# arduino_wireless_shield_rev_1_0.net
KiCad netlist of a schematic drawn in EAGLE
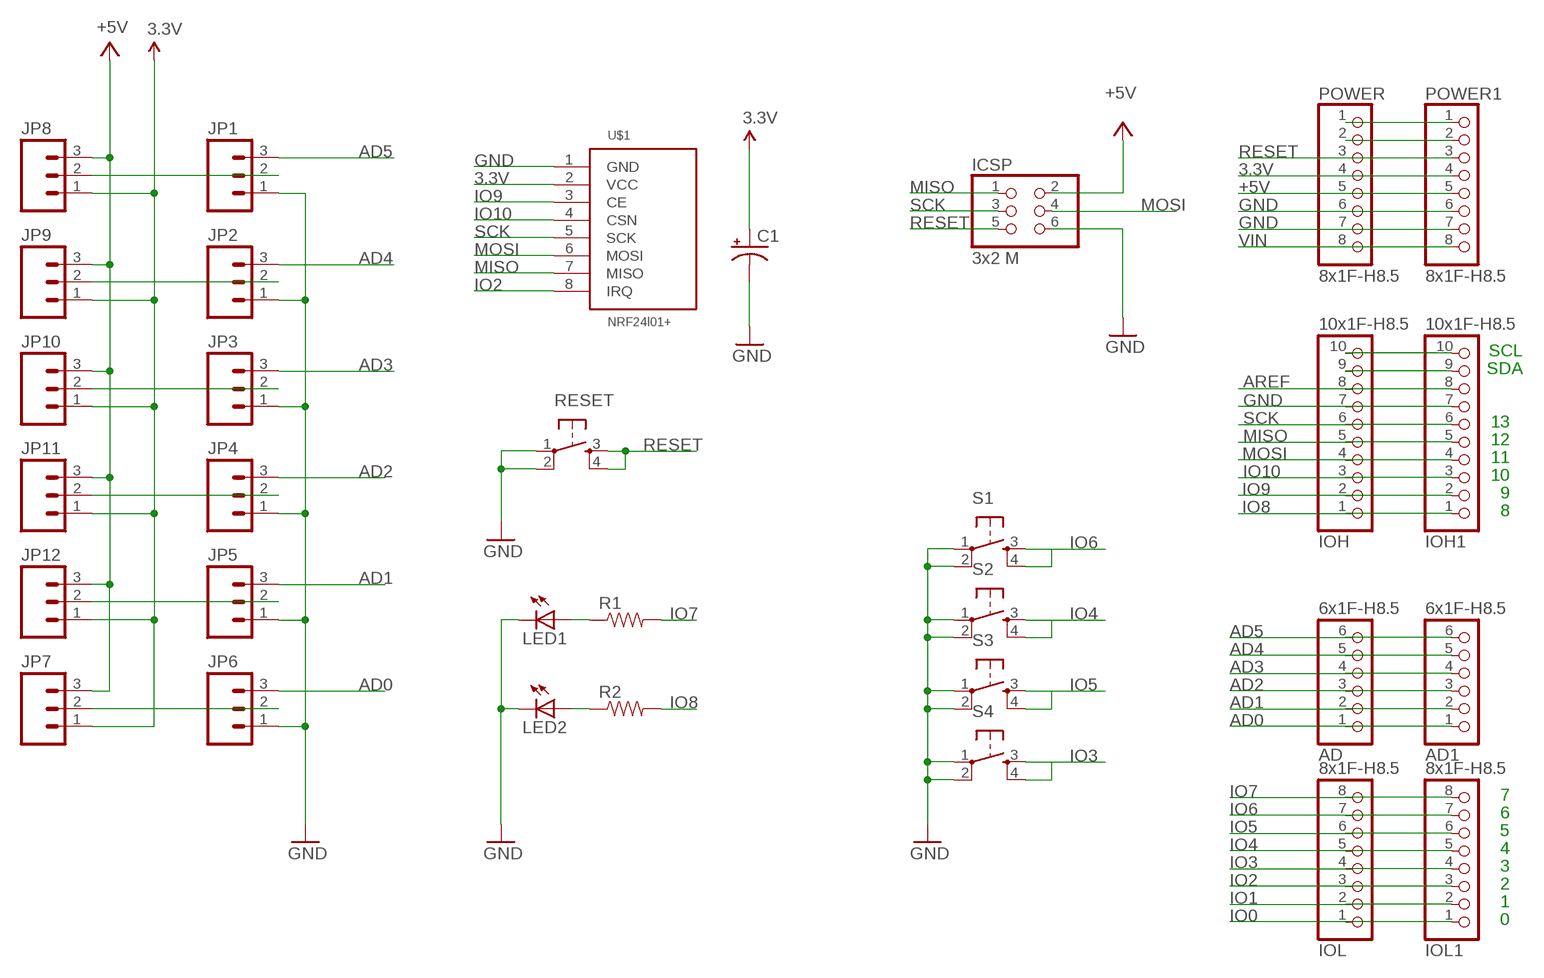
[diagram p0: schematic, sheet 1]

(export (version "E")
  (design (tool "Eeschema 10.0.6"))
  (components
    (comp (ref "AD")
      (value "6x1F-H8.5")
      (footprint "eagle-import:1X06")
      (libsource (lib "eagle-import") (part "PINHD-1X6"))
    )
    (comp (ref "AD1")
      (value "6x1F-H8.5")
      (footprint "eagle-import:1X06")
      (libsource (lib "eagle-import") (part "PINHD-1X6"))
    )
    (comp (ref "C1")
      (value "CPOL-USTT2D7")
      (footprint "eagle-import:TT2D7")
      (libsource (lib "eagle-import") (part "CPOL-USTT2D7"))
    )
    (comp (ref "ICSP")
      (value "3x2 M")
      (footprint "eagle-import:2X03")
      (libsource (lib "eagle-import") (part "PINHD-2X3"))
    )
    (comp (ref "IOH")
      (value "10x1F-H8.5")
      (footprint "eagle-import:1X10")
      (libsource (lib "eagle-import") (part "PINHD-1X10_ARD"))
    )
    (comp (ref "IOH1")
      (value "10x1F-H8.5")
      (footprint "eagle-import:1X10")
      (libsource (lib "eagle-import") (part "PINHD-1X10_ARD"))
    )
    (comp (ref "IOL")
      (value "8x1F-H8.5")
      (footprint "eagle-import:1X08")
      (libsource (lib "eagle-import") (part "PINHD-1X8"))
    )
    (comp (ref "IOL1")
      (value "8x1F-H8.5")
      (footprint "eagle-import:1X08")
      (libsource (lib "eagle-import") (part "PINHD-1X8"))
    )
    (comp (ref "JP1")
      (value "M03PTH")
      (footprint "eagle-import:1X03")
      (libsource (lib "eagle-import") (part "M03PTH"))
    )
    (comp (ref "JP2")
      (value "M03PTH")
      (footprint "eagle-import:1X03")
      (libsource (lib "eagle-import") (part "M03PTH"))
    )
    (comp (ref "JP3")
      (value "M03PTH")
      (footprint "eagle-import:1X03")
      (libsource (lib "eagle-import") (part "M03PTH"))
    )
    (comp (ref "JP4")
      (value "M03PTH")
      (footprint "eagle-import:1X03")
      (libsource (lib "eagle-import") (part "M03PTH"))
    )
    (comp (ref "JP5")
      (value "M03PTH")
      (footprint "eagle-import:1X03")
      (libsource (lib "eagle-import") (part "M03PTH"))
    )
    (comp (ref "JP6")
      (value "M03PTH")
      (footprint "eagle-import:1X03")
      (libsource (lib "eagle-import") (part "M03PTH"))
    )
    (comp (ref "JP7")
      (value "M03PTH")
      (footprint "eagle-import:1X03")
      (libsource (lib "eagle-import") (part "M03PTH"))
    )
    (comp (ref "JP8")
      (value "M03PTH")
      (footprint "eagle-import:1X03")
      (libsource (lib "eagle-import") (part "M03PTH"))
    )
    (comp (ref "JP9")
      (value "M03PTH")
      (footprint "eagle-import:1X03")
      (libsource (lib "eagle-import") (part "M03PTH"))
    )
    (comp (ref "JP10")
      (value "M03PTH")
      (footprint "eagle-import:1X03")
      (libsource (lib "eagle-import") (part "M03PTH"))
    )
    (comp (ref "JP11")
      (value "M03PTH")
      (footprint "eagle-import:1X03")
      (libsource (lib "eagle-import") (part "M03PTH"))
    )
    (comp (ref "JP12")
      (value "M03PTH")
      (footprint "eagle-import:1X03")
      (libsource (lib "eagle-import") (part "M03PTH"))
    )
    (comp (ref "LED1")
      (value "LED5MM")
      (footprint "eagle-import:LED5MM")
      (libsource (lib "eagle-import") (part "LED5MM"))
    )
    (comp (ref "LED2")
      (value "LED5MM")
      (footprint "eagle-import:LED5MM")
      (libsource (lib "eagle-import") (part "LED5MM"))
    )
    (comp (ref "POWER")
      (value "8x1F-H8.5")
      (footprint "eagle-import:1X08")
      (libsource (lib "eagle-import") (part "PINHD-1X8"))
    )
    (comp (ref "POWER1")
      (value "8x1F-H8.5")
      (footprint "eagle-import:1X08")
      (libsource (lib "eagle-import") (part "PINHD-1X8"))
    )
    (comp (ref "R1")
      (value "RESISTORPTH-1/4W")
      (footprint "eagle-import:AXIAL-0.4")
      (libsource (lib "eagle-import") (part "RESISTORPTH-1/4W"))
    )
    (comp (ref "R2")
      (value "RESISTORPTH-1/4W")
      (footprint "eagle-import:AXIAL-0.4")
      (libsource (lib "eagle-import") (part "RESISTORPTH-1/4W"))
    )
    (comp (ref "RESET")
      (value "TAC_SWITCHPTH")
      (footprint "eagle-import:TACTILE-PTH")
      (libsource (lib "eagle-import") (part "TAC_SWITCHPTH"))
    )
    (comp (ref "S1")
      (value "TAC_SWITCHPTH")
      (footprint "eagle-import:TACTILE-PTH")
      (libsource (lib "eagle-import") (part "TAC_SWITCHPTH"))
    )
    (comp (ref "S2")
      (value "TAC_SWITCHPTH")
      (footprint "eagle-import:TACTILE-PTH")
      (libsource (lib "eagle-import") (part "TAC_SWITCHPTH"))
    )
    (comp (ref "S3")
      (value "TAC_SWITCHPTH")
      (footprint "eagle-import:TACTILE-PTH")
      (libsource (lib "eagle-import") (part "TAC_SWITCHPTH"))
    )
    (comp (ref "S4")
      (value "TAC_SWITCHPTH")
      (footprint "eagle-import:TACTILE-PTH")
      (libsource (lib "eagle-import") (part "TAC_SWITCHPTH"))
    )
    (comp (ref "U$1")
      (value "NRF24L01+_MODULE")
      (footprint "eagle-import:NRF24L01+MODULE")
      (libsource (lib "eagle-import") (part "NRF24L01+_MODULE"))
    )
  )
  (nets
    (net (code "1") (name "+5V") (class "Default")
      (node (ref "ICSP") (pin "2") (pinfunction "2_2") (pintype "passive"))
      (node (ref "JP10") (pin "3") (pinfunction "3_3") (pintype "passive"))
      (node (ref "JP11") (pin "3") (pinfunction "3_3") (pintype "passive"))
      (node (ref "JP12") (pin "3") (pinfunction "3_3") (pintype "passive"))
      (node (ref "JP7") (pin "3") (pinfunction "3_3") (pintype "passive"))
      (node (ref "JP8") (pin "3") (pinfunction "3_3") (pintype "passive"))
      (node (ref "JP9") (pin "3") (pinfunction "3_3") (pintype "passive"))
      (node (ref "POWER") (pin "5") (pinfunction "5_5") (pintype "passive"))
      (node (ref "POWER1") (pin "5") (pinfunction "5_5") (pintype "passive"))
    )
    (net (code "2") (name "/AD0") (class "Default")
      (node (ref "AD") (pin "1") (pinfunction "1_1") (pintype "passive"))
      (node (ref "AD1") (pin "1") (pinfunction "1_1") (pintype "passive"))
      (node (ref "JP6") (pin "3") (pinfunction "3_3") (pintype "passive"))
    )
    (net (code "3") (name "/AD1") (class "Default")
      (node (ref "AD") (pin "2") (pinfunction "2_2") (pintype "passive"))
      (node (ref "AD1") (pin "2") (pinfunction "2_2") (pintype "passive"))
      (node (ref "JP5") (pin "3") (pinfunction "3_3") (pintype "passive"))
    )
    (net (code "4") (name "/AD2") (class "Default")
      (node (ref "AD") (pin "3") (pinfunction "3_3") (pintype "passive"))
      (node (ref "AD1") (pin "3") (pinfunction "3_3") (pintype "passive"))
      (node (ref "JP4") (pin "3") (pinfunction "3_3") (pintype "passive"))
    )
    (net (code "5") (name "/AD3") (class "Default")
      (node (ref "AD") (pin "4") (pinfunction "4_4") (pintype "passive"))
      (node (ref "AD1") (pin "4") (pinfunction "4_4") (pintype "passive"))
      (node (ref "JP3") (pin "3") (pinfunction "3_3") (pintype "passive"))
    )
    (net (code "6") (name "/AD4") (class "Default")
      (node (ref "AD") (pin "5") (pinfunction "5_5") (pintype "passive"))
      (node (ref "AD1") (pin "5") (pinfunction "5_5") (pintype "passive"))
      (node (ref "JP2") (pin "3") (pinfunction "3_3") (pintype "passive"))
    )
    (net (code "7") (name "/AD5") (class "Default")
      (node (ref "AD") (pin "6") (pinfunction "6_6") (pintype "passive"))
      (node (ref "AD1") (pin "6") (pinfunction "6_6") (pintype "passive"))
      (node (ref "JP1") (pin "3") (pinfunction "3_3") (pintype "passive"))
    )
    (net (code "8") (name "/AREF") (class "Default")
      (node (ref "IOH") (pin "8") (pinfunction "8_8") (pintype "passive"))
      (node (ref "IOH1") (pin "8") (pinfunction "8_8") (pintype "passive"))
    )
    (net (code "9") (name "/IO0") (class "Default")
      (node (ref "IOL") (pin "1") (pinfunction "1_1") (pintype "passive"))
      (node (ref "IOL1") (pin "1") (pinfunction "1_1") (pintype "passive"))
    )
    (net (code "10") (name "/IO1") (class "Default")
      (node (ref "IOL") (pin "2") (pinfunction "2_2") (pintype "passive"))
      (node (ref "IOL1") (pin "2") (pinfunction "2_2") (pintype "passive"))
    )
    (net (code "11") (name "/IO2") (class "Default")
      (node (ref "IOL") (pin "3") (pinfunction "3_3") (pintype "passive"))
      (node (ref "IOL1") (pin "3") (pinfunction "3_3") (pintype "passive"))
      (node (ref "U$1") (pin "8") (pinfunction "IRQ_8") (pintype "output"))
    )
    (net (code "12") (name "/IO3") (class "Default")
      (node (ref "IOL") (pin "4") (pinfunction "4_4") (pintype "passive"))
      (node (ref "IOL1") (pin "4") (pinfunction "4_4") (pintype "passive"))
      (node (ref "S4") (pin "3") (pinfunction "3_3") (pintype "passive"))
      (node (ref "S4") (pin "4") (pinfunction "4_4") (pintype "passive"))
    )
    (net (code "13") (name "/IO4") (class "Default")
      (node (ref "IOL") (pin "5") (pinfunction "5_5") (pintype "passive"))
      (node (ref "IOL1") (pin "5") (pinfunction "5_5") (pintype "passive"))
      (node (ref "S2") (pin "3") (pinfunction "3_3") (pintype "passive"))
      (node (ref "S2") (pin "4") (pinfunction "4_4") (pintype "passive"))
    )
    (net (code "14") (name "/IO5") (class "Default")
      (node (ref "IOL") (pin "6") (pinfunction "6_6") (pintype "passive"))
      (node (ref "IOL1") (pin "6") (pinfunction "6_6") (pintype "passive"))
      (node (ref "S3") (pin "3") (pinfunction "3_3") (pintype "passive"))
      (node (ref "S3") (pin "4") (pinfunction "4_4") (pintype "passive"))
    )
    (net (code "15") (name "/IO6") (class "Default")
      (node (ref "IOL") (pin "7") (pinfunction "7_7") (pintype "passive"))
      (node (ref "IOL1") (pin "7") (pinfunction "7_7") (pintype "passive"))
      (node (ref "S1") (pin "3") (pinfunction "3_3") (pintype "passive"))
      (node (ref "S1") (pin "4") (pinfunction "4_4") (pintype "passive"))
    )
    (net (code "16") (name "/IO7") (class "Default")
      (node (ref "IOL") (pin "8") (pinfunction "8_8") (pintype "passive"))
      (node (ref "IOL1") (pin "8") (pinfunction "8_8") (pintype "passive"))
      (node (ref "R1") (pin "P$2") (pinfunction "2_P$2") (pintype "passive"))
    )
    (net (code "17") (name "/IO8") (class "Default")
      (node (ref "IOH") (pin "1") (pinfunction "1_1") (pintype "passive"))
      (node (ref "IOH1") (pin "1") (pinfunction "1_1") (pintype "passive"))
      (node (ref "R2") (pin "P$2") (pinfunction "2_P$2") (pintype "passive"))
    )
    (net (code "18") (name "/IO9") (class "Default")
      (node (ref "IOH") (pin "2") (pinfunction "2_2") (pintype "passive"))
      (node (ref "IOH1") (pin "2") (pinfunction "2_2") (pintype "passive"))
      (node (ref "U$1") (pin "3") (pinfunction "CE_3") (pintype "input"))
    )
    (net (code "19") (name "/IO10") (class "Default")
      (node (ref "IOH") (pin "3") (pinfunction "3_3") (pintype "passive"))
      (node (ref "IOH1") (pin "3") (pinfunction "3_3") (pintype "passive"))
      (node (ref "U$1") (pin "4") (pinfunction "CSN_4") (pintype "input"))
    )
    (net (code "20") (name "/MISO") (class "Default")
      (node (ref "ICSP") (pin "1") (pinfunction "1_1") (pintype "passive"))
      (node (ref "IOH") (pin "5") (pinfunction "5_5") (pintype "passive"))
      (node (ref "IOH1") (pin "5") (pinfunction "5_5") (pintype "passive"))
      (node (ref "U$1") (pin "7") (pinfunction "MISO_7") (pintype "output"))
    )
    (net (code "21") (name "/MOSI") (class "Default")
      (node (ref "ICSP") (pin "4") (pinfunction "4_4") (pintype "passive"))
      (node (ref "IOH") (pin "4") (pinfunction "4_4") (pintype "passive"))
      (node (ref "IOH1") (pin "4") (pinfunction "4_4") (pintype "passive"))
      (node (ref "U$1") (pin "6") (pinfunction "MOSI_6") (pintype "input"))
    )
    (net (code "22") (name "/RESET") (class "Default")
      (node (ref "ICSP") (pin "5") (pinfunction "5_5") (pintype "passive"))
      (node (ref "POWER") (pin "3") (pinfunction "3_3") (pintype "passive"))
      (node (ref "POWER1") (pin "3") (pinfunction "3_3") (pintype "passive"))
      (node (ref "RESET") (pin "3") (pinfunction "3_3") (pintype "passive"))
      (node (ref "RESET") (pin "4") (pinfunction "4_4") (pintype "passive"))
    )
    (net (code "23") (name "/SCK") (class "Default")
      (node (ref "ICSP") (pin "3") (pinfunction "3_3") (pintype "passive"))
      (node (ref "IOH") (pin "6") (pinfunction "6_6") (pintype "passive"))
      (node (ref "IOH1") (pin "6") (pinfunction "6_6") (pintype "passive"))
      (node (ref "U$1") (pin "5") (pinfunction "SCK_5") (pintype "input"))
    )
    (net (code "24") (name "/VIN") (class "Default")
      (node (ref "POWER") (pin "8") (pinfunction "8_8") (pintype "passive"))
      (node (ref "POWER1") (pin "8") (pinfunction "8_8") (pintype "passive"))
    )
    (net (code "25") (name "3.3V") (class "Default")
      (node (ref "C1") (pin "+") (pinfunction "+_+") (pintype "passive"))
      (node (ref "JP10") (pin "1") (pinfunction "1_1") (pintype "passive"))
      (node (ref "JP11") (pin "1") (pinfunction "1_1") (pintype "passive"))
      (node (ref "JP12") (pin "1") (pinfunction "1_1") (pintype "passive"))
      (node (ref "JP7") (pin "1") (pinfunction "1_1") (pintype "passive"))
      (node (ref "JP8") (pin "1") (pinfunction "1_1") (pintype "passive"))
      (node (ref "JP9") (pin "1") (pinfunction "1_1") (pintype "passive"))
      (node (ref "POWER") (pin "4") (pinfunction "4_4") (pintype "passive"))
      (node (ref "POWER1") (pin "4") (pinfunction "4_4") (pintype "passive"))
      (node (ref "U$1") (pin "2") (pinfunction "VCC_2") (pintype "power_in"))
    )
    (net (code "26") (name "GND") (class "Default")
      (node (ref "C1") (pin "-") (pinfunction "-_-") (pintype "passive"))
      (node (ref "ICSP") (pin "6") (pinfunction "6_6") (pintype "passive"))
      (node (ref "IOH") (pin "7") (pinfunction "7_7") (pintype "passive"))
      (node (ref "IOH1") (pin "7") (pinfunction "7_7") (pintype "passive"))
      (node (ref "JP1") (pin "1") (pinfunction "1_1") (pintype "passive"))
      (node (ref "JP2") (pin "1") (pinfunction "1_1") (pintype "passive"))
      (node (ref "JP3") (pin "1") (pinfunction "1_1") (pintype "passive"))
      (node (ref "JP4") (pin "1") (pinfunction "1_1") (pintype "passive"))
      (node (ref "JP5") (pin "1") (pinfunction "1_1") (pintype "passive"))
      (node (ref "JP6") (pin "1") (pinfunction "1_1") (pintype "passive"))
      (node (ref "LED1") (pin "K") (pinfunction "C_K") (pintype "passive"))
      (node (ref "LED2") (pin "K") (pinfunction "C_K") (pintype "passive"))
      (node (ref "POWER") (pin "6") (pinfunction "6_6") (pintype "passive"))
      (node (ref "POWER") (pin "7") (pinfunction "7_7") (pintype "passive"))
      (node (ref "POWER1") (pin "6") (pinfunction "6_6") (pintype "passive"))
      (node (ref "POWER1") (pin "7") (pinfunction "7_7") (pintype "passive"))
      (node (ref "RESET") (pin "1") (pinfunction "1_1") (pintype "passive"))
      (node (ref "RESET") (pin "2") (pinfunction "2_2") (pintype "passive"))
      (node (ref "S1") (pin "1") (pinfunction "1_1") (pintype "passive"))
      (node (ref "S1") (pin "2") (pinfunction "2_2") (pintype "passive"))
      (node (ref "S2") (pin "1") (pinfunction "1_1") (pintype "passive"))
      (node (ref "S2") (pin "2") (pinfunction "2_2") (pintype "passive"))
      (node (ref "S3") (pin "1") (pinfunction "1_1") (pintype "passive"))
      (node (ref "S3") (pin "2") (pinfunction "2_2") (pintype "passive"))
      (node (ref "S4") (pin "1") (pinfunction "1_1") (pintype "passive"))
      (node (ref "S4") (pin "2") (pinfunction "2_2") (pintype "passive"))
      (node (ref "U$1") (pin "1") (pinfunction "GND_1") (pintype "power_in"))
    )
    (net (code "27") (name "Net-(IOH-Pad9)") (class "Default")
      (node (ref "IOH") (pin "9") (pinfunction "9_9") (pintype "passive"))
      (node (ref "IOH1") (pin "9") (pinfunction "9_9") (pintype "passive"))
    )
    (net (code "28") (name "Net-(IOH-Pad10)") (class "Default")
      (node (ref "IOH") (pin "10") (pinfunction "10_10") (pintype "passive"))
      (node (ref "IOH1") (pin "10") (pinfunction "10_10") (pintype "passive"))
    )
    (net (code "29") (name "Net-(JP1-Pad2)") (class "Default")
      (node (ref "JP1") (pin "2") (pinfunction "2_2") (pintype "passive"))
      (node (ref "JP8") (pin "2") (pinfunction "2_2") (pintype "passive"))
    )
    (net (code "30") (name "Net-(JP2-Pad2)") (class "Default")
      (node (ref "JP2") (pin "2") (pinfunction "2_2") (pintype "passive"))
      (node (ref "JP9") (pin "2") (pinfunction "2_2") (pintype "passive"))
    )
    (net (code "31") (name "Net-(JP6-Pad2)") (class "Default")
      (node (ref "JP6") (pin "2") (pinfunction "2_2") (pintype "passive"))
      (node (ref "JP7") (pin "2") (pinfunction "2_2") (pintype "passive"))
    )
    (net (code "32") (name "Net-(JP10-Pad2)") (class "Default")
      (node (ref "JP10") (pin "2") (pinfunction "2_2") (pintype "passive"))
      (node (ref "JP3") (pin "2") (pinfunction "2_2") (pintype "passive"))
    )
    (net (code "33") (name "Net-(JP11-Pad2)") (class "Default")
      (node (ref "JP11") (pin "2") (pinfunction "2_2") (pintype "passive"))
      (node (ref "JP4") (pin "2") (pinfunction "2_2") (pintype "passive"))
    )
    (net (code "34") (name "Net-(JP12-Pad2)") (class "Default")
      (node (ref "JP12") (pin "2") (pinfunction "2_2") (pintype "passive"))
      (node (ref "JP5") (pin "2") (pinfunction "2_2") (pintype "passive"))
    )
    (net (code "35") (name "Net-(POWER-Pad1)") (class "Default")
      (node (ref "POWER") (pin "1") (pinfunction "1_1") (pintype "passive"))
      (node (ref "POWER1") (pin "1") (pinfunction "1_1") (pintype "passive"))
    )
    (net (code "36") (name "Net-(POWER-Pad2)") (class "Default")
      (node (ref "POWER") (pin "2") (pinfunction "2_2") (pintype "passive"))
      (node (ref "POWER1") (pin "2") (pinfunction "2_2") (pintype "passive"))
    )
    (net (code "37") (name "Net-(R1-1)") (class "Default")
      (node (ref "LED1") (pin "A") (pinfunction "A_A") (pintype "passive"))
      (node (ref "R1") (pin "P$1") (pinfunction "1_P$1") (pintype "passive"))
    )
    (net (code "38") (name "Net-(R2-1)") (class "Default")
      (node (ref "LED2") (pin "A") (pinfunction "A_A") (pintype "passive"))
      (node (ref "R2") (pin "P$1") (pinfunction "1_P$1") (pintype "passive"))
    )
  )
)
